# ProgrammateurFilPilote_1_2.net
KiCad netlist of a schematic drawn in EAGLE
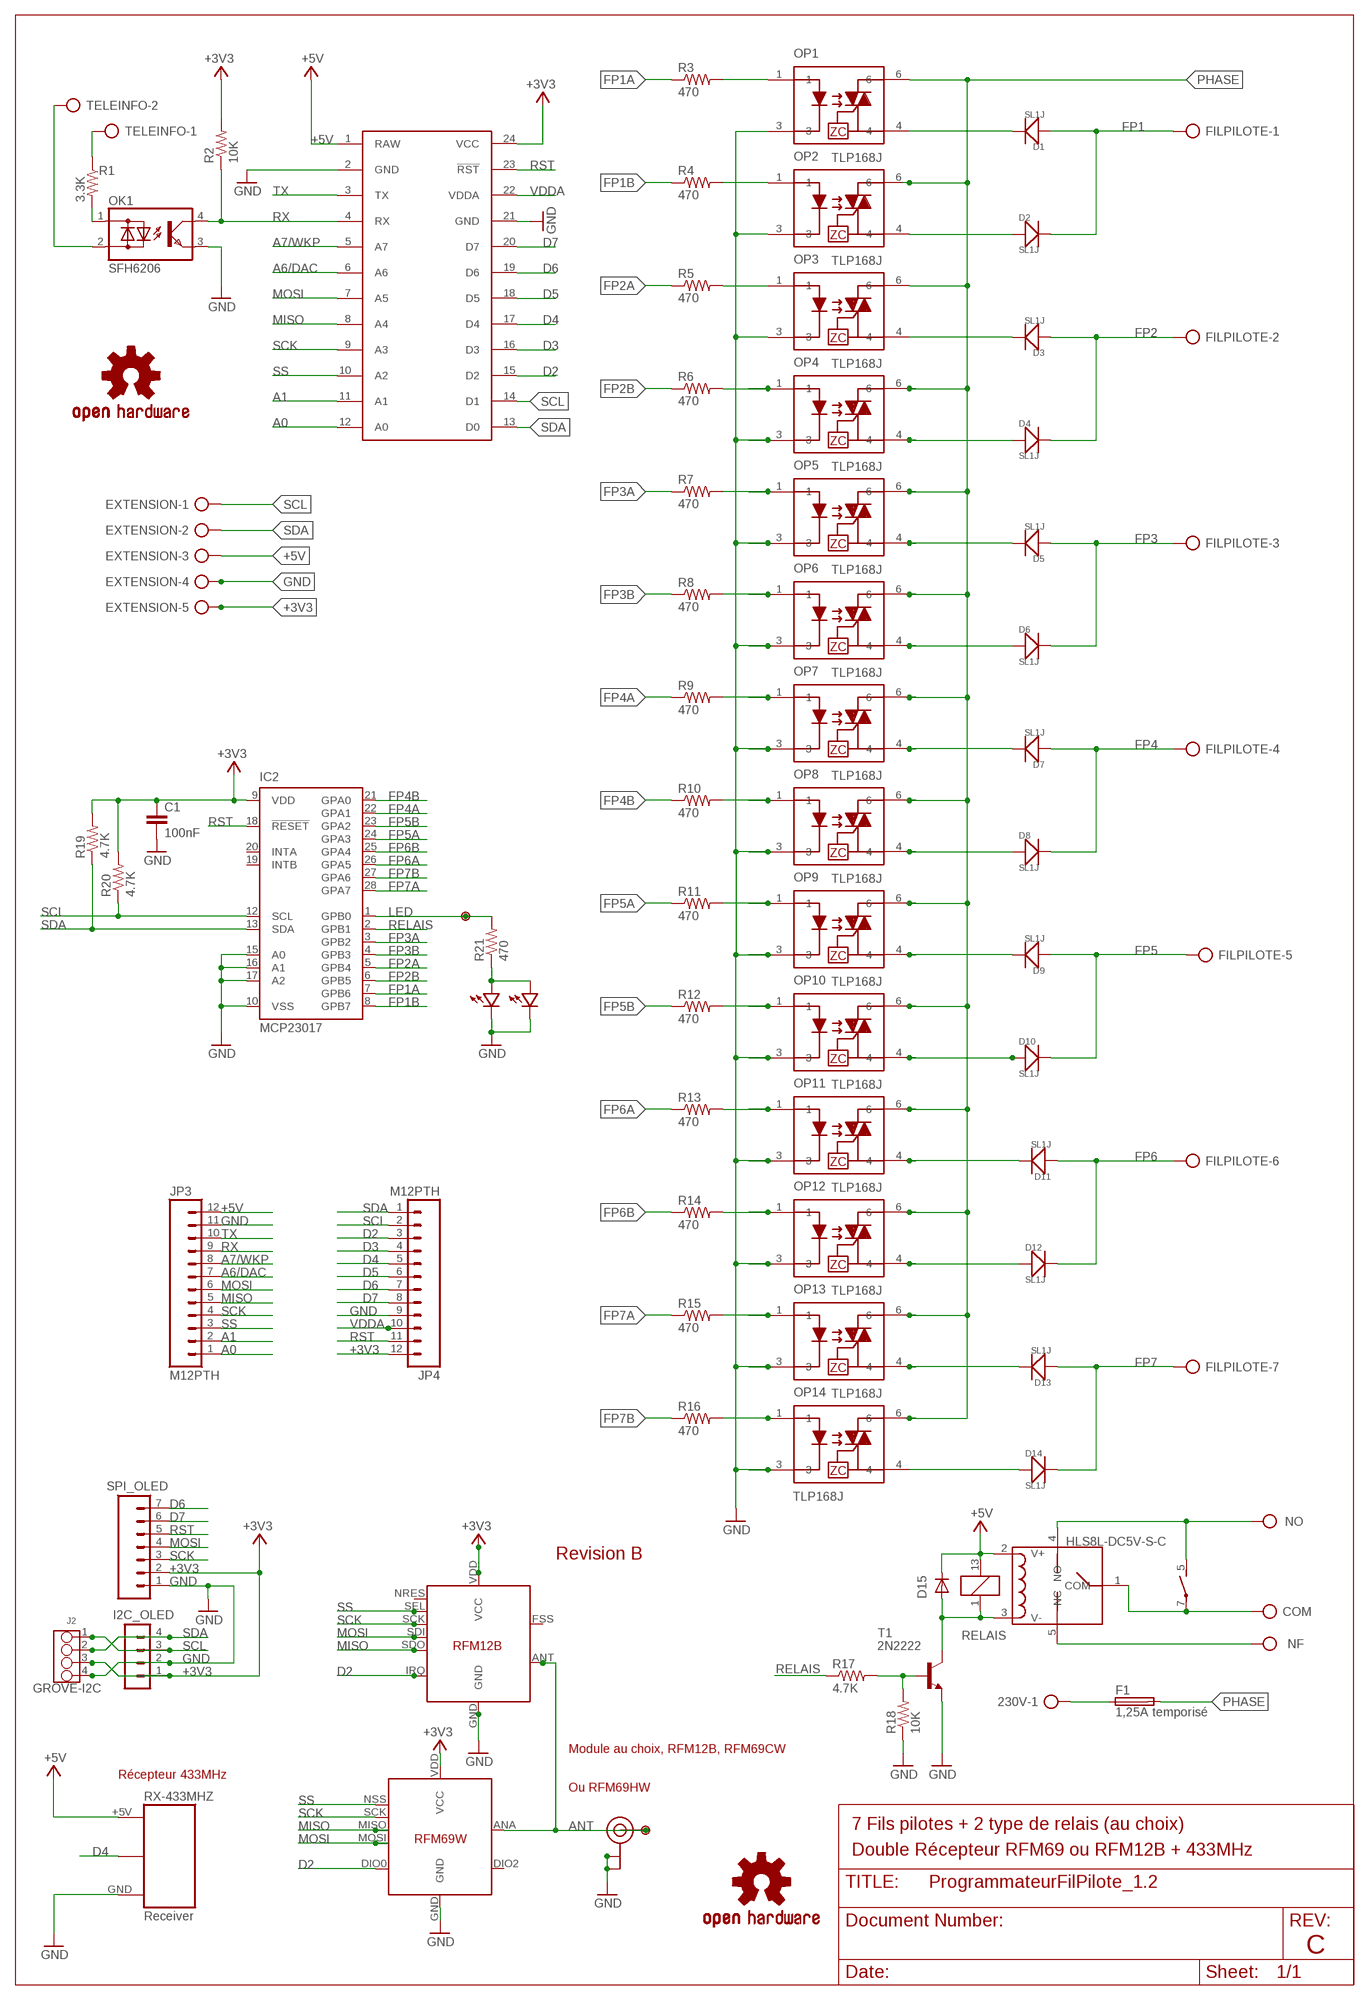
[diagram p0: schematic, sheet 1]

(export (version "E")
  (design (tool "Eeschema 10.0.6"))
  (components
    (comp (ref "230V")
      (value "AK500/2")
      (footprint "eagle-import:AK500_2")
      (libsource (lib "eagle-import") (part "AK500/2"))
    )
    (comp (ref "C1")
      (value "100nF")
      (footprint "eagle-import:1206-CAP")
      (libsource (lib "eagle-import") (part "CAP'1206-CAP'"))
    )
    (comp (ref "D1")
      (value "SL1J")
      (footprint "eagle-import:DO-214AC")
      (libsource (lib "eagle-import") (part "DIODE-SMA"))
    )
    (comp (ref "D2")
      (value "SL1J")
      (footprint "eagle-import:DO-214AC")
      (libsource (lib "eagle-import") (part "DIODE-SMA"))
    )
    (comp (ref "D3")
      (value "SL1J")
      (footprint "eagle-import:DO-214AC")
      (libsource (lib "eagle-import") (part "DIODE-SMA"))
    )
    (comp (ref "D4")
      (value "SL1J")
      (footprint "eagle-import:DO-214AC")
      (libsource (lib "eagle-import") (part "DIODE-SMA"))
    )
    (comp (ref "D5")
      (value "SL1J")
      (footprint "eagle-import:DO-214AC")
      (libsource (lib "eagle-import") (part "DIODE-SMA"))
    )
    (comp (ref "D6")
      (value "SL1J")
      (footprint "eagle-import:DO-214AC")
      (libsource (lib "eagle-import") (part "DIODE-SMA"))
    )
    (comp (ref "D7")
      (value "SL1J")
      (footprint "eagle-import:DO-214AC")
      (libsource (lib "eagle-import") (part "DIODE-SMA"))
    )
    (comp (ref "D8")
      (value "SL1J")
      (footprint "eagle-import:DO-214AC")
      (libsource (lib "eagle-import") (part "DIODE-SMA"))
    )
    (comp (ref "D9")
      (value "SL1J")
      (footprint "eagle-import:DO-214AC")
      (libsource (lib "eagle-import") (part "DIODE-SMA"))
    )
    (comp (ref "D10")
      (value "SL1J")
      (footprint "eagle-import:DO-214AC")
      (libsource (lib "eagle-import") (part "DIODE-SMA"))
    )
    (comp (ref "D11")
      (value "SL1J")
      (footprint "eagle-import:DO-214AC")
      (libsource (lib "eagle-import") (part "DIODE-SMA"))
    )
    (comp (ref "D12")
      (value "SL1J")
      (footprint "eagle-import:DO-214AC")
      (libsource (lib "eagle-import") (part "DIODE-SMA"))
    )
    (comp (ref "D13")
      (value "SL1J")
      (footprint "eagle-import:DO-214AC")
      (libsource (lib "eagle-import") (part "DIODE-SMA"))
    )
    (comp (ref "D14")
      (value "SL1J")
      (footprint "eagle-import:DO-214AC")
      (libsource (lib "eagle-import") (part "DIODE-SMA"))
    )
    (comp (ref "D15")
      (value "CGRM4001-G")
      (footprint "eagle-import:SOD-123_MINI-SMA")
      (libsource (lib "eagle-import") (part "CGRM400-G1"))
    )
    (comp (ref "EXTENSION")
      (value "AK500/5")
      (footprint "eagle-import:AK500_5")
      (libsource (lib "eagle-import") (part "AK500/5"))
    )
    (comp (ref "F1")
      (value "1,25A temporisé")
      (footprint "eagle-import:TE5")
      (libsource (lib "eagle-import") (part "TE5"))
    )
    (comp (ref "FILPILOTE")
      (value "AK500/7")
      (footprint "eagle-import:AK500_7")
      (libsource (lib "eagle-import") (part "AK500/7"))
    )
    (comp (ref "I2C_OLED")
      (value "CON_HEADER_1X04'SMALL''")
      (footprint "eagle-import:M1X4")
      (libsource (lib "eagle-import") (part "CON_HEADER_1X04'SMALL''"))
    )
    (comp (ref "IC2")
      (value "MCP23017")
      (footprint "eagle-import:DIL28-3")
      (libsource (lib "eagle-import") (part "MCP23017SP"))
    )
    (comp (ref "J2")
      (value "GROVE-I2C")
      (footprint "eagle-import:4P-2.0")
      (libsource (lib "eagle-import") (part "GROVE-4P-2.0-3470130P1"))
    )
    (comp (ref "JP3")
      (value "M12PTH")
      (footprint "eagle-import:1X12-SMALL-PADS")
      (libsource (lib "eagle-import") (part "M12PTH"))
    )
    (comp (ref "JP4")
      (value "M12PTH")
      (footprint "eagle-import:1X12-SMALL-PADS")
      (libsource (lib "eagle-import") (part "M12PTH"))
    )
    (comp (ref "L")
      (value "LED0805-LARGE")
      (footprint "eagle-import:0805-LED-LARGEPADS")
      (libsource (lib "eagle-import") (part "LED0805-LARGE"))
    )
    (comp (ref "LED")
      (value "LED3MMNOSILK")
      (footprint "eagle-import:LED3MM_NOSILK")
      (libsource (lib "eagle-import") (part "LED3MMNOSILK"))
    )
    (comp (ref "LOGO1")
      (value "OSHW-LOGOL")
      (footprint "eagle-import:OSHW-LOGO-L")
      (libsource (lib "eagle-import") (part "OSHW-LOGOL"))
    )
    (comp (ref "LOGO2")
      (value "OSHW-LOGOL")
      (footprint "eagle-import:OSHW-LOGO-L")
      (libsource (lib "eagle-import") (part "OSHW-LOGOL"))
    )
    (comp (ref "OK1")
      (value "SFH6206")
      (footprint "eagle-import:DIL4-SMD")
      (fields (field (name "MF") "VISHAY/TELEFUNKEN") (field (name "MPN") "SFH6206-3"))
      (libsource (lib "eagle-import") (part "SFH6206"))
    )
    (comp (ref "OP1")
      (value "TLP168J")
      (footprint "eagle-import:MFSOP-4-HANDSOLDER")
      (libsource (lib "eagle-import") (part "TLP168JBIGPAD"))
    )
    (comp (ref "OP2")
      (value "TLP168J")
      (footprint "eagle-import:MFSOP-4-HANDSOLDER")
      (libsource (lib "eagle-import") (part "TLP168JBIGPAD"))
    )
    (comp (ref "OP3")
      (value "TLP168J")
      (footprint "eagle-import:MFSOP-4-HANDSOLDER")
      (libsource (lib "eagle-import") (part "TLP168JBIGPAD"))
    )
    (comp (ref "OP4")
      (value "TLP168J")
      (footprint "eagle-import:MFSOP-4-HANDSOLDER")
      (libsource (lib "eagle-import") (part "TLP168JBIGPAD"))
    )
    (comp (ref "OP5")
      (value "TLP168J")
      (footprint "eagle-import:MFSOP-4-HANDSOLDER")
      (libsource (lib "eagle-import") (part "TLP168JBIGPAD"))
    )
    (comp (ref "OP6")
      (value "TLP168J")
      (footprint "eagle-import:MFSOP-4-HANDSOLDER")
      (libsource (lib "eagle-import") (part "TLP168JBIGPAD"))
    )
    (comp (ref "OP7")
      (value "TLP168J")
      (footprint "eagle-import:MFSOP-4-HANDSOLDER")
      (libsource (lib "eagle-import") (part "TLP168JBIGPAD"))
    )
    (comp (ref "OP8")
      (value "TLP168J")
      (footprint "eagle-import:MFSOP-4-HANDSOLDER")
      (libsource (lib "eagle-import") (part "TLP168JBIGPAD"))
    )
    (comp (ref "OP9")
      (value "TLP168J")
      (footprint "eagle-import:MFSOP-4-HANDSOLDER")
      (libsource (lib "eagle-import") (part "TLP168JBIGPAD"))
    )
    (comp (ref "OP10")
      (value "TLP168J")
      (footprint "eagle-import:MFSOP-4-HANDSOLDER")
      (libsource (lib "eagle-import") (part "TLP168JBIGPAD"))
    )
    (comp (ref "OP11")
      (value "TLP168J")
      (footprint "eagle-import:MFSOP-4-HANDSOLDER")
      (libsource (lib "eagle-import") (part "TLP168JBIGPAD"))
    )
    (comp (ref "OP12")
      (value "TLP168J")
      (footprint "eagle-import:MFSOP-4-HANDSOLDER")
      (libsource (lib "eagle-import") (part "TLP168JBIGPAD"))
    )
    (comp (ref "OP13")
      (value "TLP168J")
      (footprint "eagle-import:MFSOP-4-HANDSOLDER")
      (libsource (lib "eagle-import") (part "TLP168JBIGPAD"))
    )
    (comp (ref "OP14")
      (value "TLP168J")
      (footprint "eagle-import:MFSOP-4-HANDSOLDER")
      (libsource (lib "eagle-import") (part "TLP168JBIGPAD"))
    )
    (comp (ref "P1")
      (value "PADSMALL")
      (footprint "eagle-import:PAD-SMALL")
      (libsource (lib "eagle-import") (part "PADSMALL"))
    )
    (comp (ref "P2")
      (value "PADSMALL")
      (footprint "eagle-import:PAD-SMALL")
      (libsource (lib "eagle-import") (part "PADSMALL"))
    )
    (comp (ref "R1")
      (value "3.3K")
      (footprint "eagle-import:1206-RES")
      (libsource (lib "eagle-import") (part "RESISTOR'1206-RES''"))
    )
    (comp (ref "R2")
      (value "10K")
      (footprint "eagle-import:1206-RES")
      (libsource (lib "eagle-import") (part "RESISTOR'1206-RES''"))
    )
    (comp (ref "R3")
      (value "470")
      (footprint "eagle-import:1206-RES")
      (libsource (lib "eagle-import") (part "RESISTOR'1206-RES''"))
    )
    (comp (ref "R4")
      (value "470")
      (footprint "eagle-import:1206-RES")
      (libsource (lib "eagle-import") (part "RESISTOR'1206-RES''"))
    )
    (comp (ref "R5")
      (value "470")
      (footprint "eagle-import:1206-RES")
      (libsource (lib "eagle-import") (part "RESISTOR'1206-RES''"))
    )
    (comp (ref "R6")
      (value "470")
      (footprint "eagle-import:1206-RES")
      (libsource (lib "eagle-import") (part "RESISTOR'1206-RES''"))
    )
    (comp (ref "R7")
      (value "470")
      (footprint "eagle-import:1206-RES")
      (libsource (lib "eagle-import") (part "RESISTOR'1206-RES''"))
    )
    (comp (ref "R8")
      (value "470")
      (footprint "eagle-import:1206-RES")
      (libsource (lib "eagle-import") (part "RESISTOR'1206-RES''"))
    )
    (comp (ref "R9")
      (value "470")
      (footprint "eagle-import:1206-RES")
      (libsource (lib "eagle-import") (part "RESISTOR'1206-RES''"))
    )
    (comp (ref "R10")
      (value "470")
      (footprint "eagle-import:1206-RES")
      (libsource (lib "eagle-import") (part "RESISTOR'1206-RES''"))
    )
    (comp (ref "R11")
      (value "470")
      (footprint "eagle-import:1206-RES")
      (libsource (lib "eagle-import") (part "RESISTOR'1206-RES''"))
    )
    (comp (ref "R12")
      (value "470")
      (footprint "eagle-import:1206-RES")
      (libsource (lib "eagle-import") (part "RESISTOR'1206-RES''"))
    )
    (comp (ref "R13")
      (value "470")
      (footprint "eagle-import:1206-RES")
      (libsource (lib "eagle-import") (part "RESISTOR'1206-RES''"))
    )
    (comp (ref "R14")
      (value "470")
      (footprint "eagle-import:1206-RES")
      (libsource (lib "eagle-import") (part "RESISTOR'1206-RES''"))
    )
    (comp (ref "R15")
      (value "470")
      (footprint "eagle-import:1206-RES")
      (libsource (lib "eagle-import") (part "RESISTOR'1206-RES''"))
    )
    (comp (ref "R16")
      (value "470")
      (footprint "eagle-import:1206-RES")
      (libsource (lib "eagle-import") (part "RESISTOR'1206-RES''"))
    )
    (comp (ref "R17")
      (value "4.7K")
      (footprint "eagle-import:1206-RES")
      (libsource (lib "eagle-import") (part "RESISTOR'1206-RES''"))
    )
    (comp (ref "R18")
      (value "10K")
      (footprint "eagle-import:1206-RES")
      (libsource (lib "eagle-import") (part "RESISTOR'1206-RES''"))
    )
    (comp (ref "R19")
      (value "4.7K")
      (footprint "eagle-import:1206-RES")
      (libsource (lib "eagle-import") (part "RESISTOR'1206-RES''"))
    )
    (comp (ref "R20")
      (value "4.7K")
      (footprint "eagle-import:1206-RES")
      (libsource (lib "eagle-import") (part "RESISTOR'1206-RES''"))
    )
    (comp (ref "R21")
      (value "470")
      (footprint "eagle-import:1206-RES")
      (libsource (lib "eagle-import") (part "RESISTOR'1206-RES''"))
    )
    (comp (ref "RELAIS")
      (value "Relais G6D")
      (footprint "eagle-import:G6D")
      (libsource (lib "eagle-import") (part "G6D?-1A-ASI12VDC"))
    )
    (comp (ref "RL")
      (value "AK500/2")
      (footprint "eagle-import:AK500_2")
      (libsource (lib "eagle-import") (part "AK500/2"))
    )
    (comp (ref "RX-433MHZ")
      (value "Receiver")
      (footprint "eagle-import:RF-LINK_RX")
      (libsource (lib "eagle-import") (part "RF-LINK_RX"))
    )
    (comp (ref "SPARKCORE")
      (value "SPARK_CORECORE")
      (footprint "eagle-import:SPARK_CORE")
      (libsource (lib "eagle-import") (part "SPARK_CORECORE"))
    )
    (comp (ref "SPI_OLED")
      (value "CON_HEADER_1X07'SMALL'")
      (footprint "eagle-import:M1X7")
      (libsource (lib "eagle-import") (part "CON_HEADER_1X07'SMALL'"))
    )
    (comp (ref "SW1")
      (value "HLS8L-DC5V-S-C")
      (footprint "eagle-import:5P-L19.0XW15.0XH15.0MM")
      (libsource (lib "eagle-import") (part "RELAY-HLS8L-DC5V-S-C-315030000"))
    )
    (comp (ref "T1")
      (value "2N2222")
      (footprint "eagle-import:TO92-EBC")
      (libsource (lib "eagle-import") (part "-NPN-TO92-EBC2N2222"))
    )
    (comp (ref "TELEINFO")
      (value "AK500/2")
      (footprint "eagle-import:AK500_2")
      (libsource (lib "eagle-import") (part "AK500/2"))
    )
    (comp (ref "U$2")
      (value "RFM12B")
      (footprint "eagle-import:RFM12B-MINPADS")
      (libsource (lib "eagle-import") (part "RFM12B"))
    )
    (comp (ref "U$3")
      (value "RFM69W")
      (footprint "eagle-import:RFM69W-MINPADS")
      (libsource (lib "eagle-import") (part "RFM69W"))
    )
    (comp (ref "U-FL")
      (value "U.FL")
      (footprint "eagle-import:U.FL")
      (libsource (lib "eagle-import") (part "U.FL"))
    )
  )
  (nets
    (net (code "1") (name "+3V3") (class "Default")
      (node (ref "C1") (pin "1") (pinfunction "1_1") (pintype "passive"))
      (node (ref "EXTENSION") (pin "5") (pinfunction "KL_5") (pintype "passive"))
      (node (ref "I2C_OLED") (pin "1") (pinfunction "1_1") (pintype "passive"))
      (node (ref "IC2") (pin "9") (pinfunction "VDD_9") (pintype "power_in"))
      (node (ref "J2") (pin "3") (pinfunction "3_3") (pintype "bidirectional"))
      (node (ref "JP4") (pin "12") (pinfunction "12_12") (pintype "passive"))
      (node (ref "R19") (pin "2") (pinfunction "2_2") (pintype "passive"))
      (node (ref "R2") (pin "2") (pinfunction "2_2") (pintype "passive"))
      (node (ref "R20") (pin "2") (pinfunction "2_2") (pintype "passive"))
      (node (ref "SPARKCORE") (pin "24") (pinfunction "VCC_24") (pintype "power_in"))
      (node (ref "SPI_OLED") (pin "2") (pinfunction "2_2") (pintype "passive"))
      (node (ref "U$2") (pin "VDD") (pinfunction "VCC_VDD") (pintype "power_in"))
      (node (ref "U$3") (pin "VDD") (pinfunction "VCC_VDD") (pintype "power_in"))
    )
    (net (code "2") (name "+5V") (class "Default")
      (node (ref "D15") (pin "C") (pinfunction "C_C") (pintype "passive"))
      (node (ref "EXTENSION") (pin "3") (pinfunction "KL_3") (pintype "passive"))
      (node (ref "JP3") (pin "12") (pinfunction "12_12") (pintype "passive"))
      (node (ref "RELAIS") (pin "13") (pinfunction "2_13") (pintype "passive"))
      (node (ref "RX-433MHZ") (pin "+5V") (pinfunction "+5V_+5V") (pintype "power_in"))
      (node (ref "SPARKCORE") (pin "1") (pinfunction "RAW_1") (pintype "power_in"))
      (node (ref "SW1") (pin "2") (pinfunction "V+_2") (pintype "bidirectional"))
    )
    (net (code "3") (name "/A0") (class "Default")
      (node (ref "JP3") (pin "1") (pinfunction "1_1") (pintype "passive"))
      (node (ref "SPARKCORE") (pin "12") (pinfunction "A0_12") (pintype "bidirectional"))
    )
    (net (code "4") (name "/A1") (class "Default")
      (node (ref "JP3") (pin "2") (pinfunction "2_2") (pintype "passive"))
      (node (ref "SPARKCORE") (pin "11") (pinfunction "A1_11") (pintype "bidirectional"))
    )
    (net (code "5") (name "/A6{slash}DAC") (class "Default")
      (node (ref "JP3") (pin "7") (pinfunction "7_7") (pintype "passive"))
      (node (ref "SPARKCORE") (pin "6") (pinfunction "A6_6") (pintype "bidirectional"))
    )
    (net (code "6") (name "/A7{slash}WKP") (class "Default")
      (node (ref "JP3") (pin "8") (pinfunction "8_8") (pintype "passive"))
      (node (ref "SPARKCORE") (pin "5") (pinfunction "A7_5") (pintype "bidirectional"))
    )
    (net (code "7") (name "/ANT") (class "Default")
      (node (ref "P1") (pin "1") (pinfunction "1_1") (pintype "bidirectional"))
      (node (ref "U$2") (pin "ANT") (pinfunction "ANT_ANT") (pintype "passive"))
      (node (ref "U$3") (pin "ANA") (pinfunction "ANT_ANA") (pintype "passive"))
      (node (ref "U-FL") (pin "3") (pinfunction "SIGNAL_3") (pintype "passive"))
    )
    (net (code "8") (name "/COM") (class "Default")
      (node (ref "RELAIS") (pin "7") (pinfunction "P_7") (pintype "passive"))
      (node (ref "RL") (pin "1") (pinfunction "KL_1") (pintype "passive"))
      (node (ref "SW1") (pin "1") (pinfunction "COM_1") (pintype "bidirectional"))
    )
    (net (code "9") (name "/D2") (class "Default")
      (node (ref "JP4") (pin "3") (pinfunction "3_3") (pintype "passive"))
      (node (ref "SPARKCORE") (pin "15") (pinfunction "D2_15") (pintype "bidirectional"))
      (node (ref "U$2") (pin "IRQ") (pinfunction "IRQ_IRQ") (pintype "open_collector"))
      (node (ref "U$3") (pin "DIO0") (pinfunction "DIO0_DIO0") (pintype "open_collector"))
    )
    (net (code "10") (name "/D3") (class "Default")
      (node (ref "JP4") (pin "4") (pinfunction "4_4") (pintype "passive"))
      (node (ref "SPARKCORE") (pin "16") (pinfunction "D3_16") (pintype "bidirectional"))
    )
    (net (code "11") (name "/D4") (class "Default")
      (node (ref "JP4") (pin "5") (pinfunction "5_5") (pintype "passive"))
      (node (ref "RX-433MHZ") (pin "DATA@1") (pinfunction "DATA_DATA@1") (pintype "output"))
      (node (ref "RX-433MHZ") (pin "DATA@2") (pinfunction "DATA_DATA@2") (pintype "output"))
      (node (ref "SPARKCORE") (pin "17") (pinfunction "D4_17") (pintype "bidirectional"))
    )
    (net (code "12") (name "/D5") (class "Default")
      (node (ref "JP4") (pin "6") (pinfunction "6_6") (pintype "passive"))
      (node (ref "SPARKCORE") (pin "18") (pinfunction "D5_18") (pintype "bidirectional"))
    )
    (net (code "13") (name "/D6") (class "Default")
      (node (ref "JP4") (pin "7") (pinfunction "7_7") (pintype "passive"))
      (node (ref "SPARKCORE") (pin "19") (pinfunction "D6_19") (pintype "bidirectional"))
      (node (ref "SPI_OLED") (pin "7") (pinfunction "7_7") (pintype "passive"))
    )
    (net (code "14") (name "/D7") (class "Default")
      (node (ref "JP4") (pin "8") (pinfunction "8_8") (pintype "passive"))
      (node (ref "SPARKCORE") (pin "20") (pinfunction "D7_20") (pintype "bidirectional"))
      (node (ref "SPI_OLED") (pin "6") (pinfunction "6_6") (pintype "passive"))
    )
    (net (code "15") (name "/FP1") (class "Default")
      (node (ref "D1") (pin "1") (pinfunction "+_1") (pintype "passive"))
      (node (ref "D2") (pin "2") (pinfunction "-_2") (pintype "passive"))
      (node (ref "FILPILOTE") (pin "1") (pinfunction "KL_1") (pintype "passive"))
    )
    (net (code "16") (name "/FP2") (class "Default")
      (node (ref "D3") (pin "1") (pinfunction "+_1") (pintype "passive"))
      (node (ref "D4") (pin "2") (pinfunction "-_2") (pintype "passive"))
      (node (ref "FILPILOTE") (pin "2") (pinfunction "KL_2") (pintype "passive"))
    )
    (net (code "17") (name "/FP3") (class "Default")
      (node (ref "D5") (pin "1") (pinfunction "+_1") (pintype "passive"))
      (node (ref "D6") (pin "2") (pinfunction "-_2") (pintype "passive"))
      (node (ref "FILPILOTE") (pin "3") (pinfunction "KL_3") (pintype "passive"))
    )
    (net (code "18") (name "/FP4") (class "Default")
      (node (ref "D7") (pin "1") (pinfunction "+_1") (pintype "passive"))
      (node (ref "D8") (pin "2") (pinfunction "-_2") (pintype "passive"))
      (node (ref "FILPILOTE") (pin "4") (pinfunction "KL_4") (pintype "passive"))
    )
    (net (code "19") (name "/FP5") (class "Default")
      (node (ref "D10") (pin "2") (pinfunction "-_2") (pintype "passive"))
      (node (ref "D9") (pin "1") (pinfunction "+_1") (pintype "passive"))
      (node (ref "FILPILOTE") (pin "5") (pinfunction "KL_5") (pintype "passive"))
    )
    (net (code "20") (name "/FP6") (class "Default")
      (node (ref "D11") (pin "1") (pinfunction "+_1") (pintype "passive"))
      (node (ref "D12") (pin "2") (pinfunction "-_2") (pintype "passive"))
      (node (ref "FILPILOTE") (pin "6") (pinfunction "KL_6") (pintype "passive"))
    )
    (net (code "21") (name "/FP7") (class "Default")
      (node (ref "D13") (pin "1") (pinfunction "+_1") (pintype "passive"))
      (node (ref "D14") (pin "2") (pinfunction "-_2") (pintype "passive"))
      (node (ref "FILPILOTE") (pin "7") (pinfunction "KL_7") (pintype "passive"))
    )
    (net (code "22") (name "/LED") (class "Default")
      (node (ref "IC2") (pin "1") (pinfunction "GPB0_1") (pintype "bidirectional"))
      (node (ref "P2") (pin "1") (pinfunction "1_1") (pintype "bidirectional"))
      (node (ref "R21") (pin "2") (pinfunction "2_2") (pintype "passive"))
    )
    (net (code "23") (name "/MISO") (class "Default")
      (node (ref "JP3") (pin "5") (pinfunction "5_5") (pintype "passive"))
      (node (ref "SPARKCORE") (pin "8") (pinfunction "A4_8") (pintype "bidirectional"))
      (node (ref "U$2") (pin "SDO") (pinfunction "SDO_SDO") (pintype "output"))
      (node (ref "U$3") (pin "MISO") (pinfunction "MISO_MISO") (pintype "input"))
    )
    (net (code "24") (name "/MOSI") (class "Default")
      (node (ref "JP3") (pin "6") (pinfunction "6_6") (pintype "passive"))
      (node (ref "SPARKCORE") (pin "7") (pinfunction "A5_7") (pintype "bidirectional"))
      (node (ref "SPI_OLED") (pin "4") (pinfunction "4_4") (pintype "passive"))
      (node (ref "U$2") (pin "SDI") (pinfunction "SDI_SDI") (pintype "input"))
      (node (ref "U$3") (pin "MOSI") (pinfunction "MOSI_MOSI") (pintype "output"))
    )
    (net (code "25") (name "/NF") (class "Default")
      (node (ref "RL") (pin "2") (pinfunction "KL_2") (pintype "passive"))
      (node (ref "SW1") (pin "5") (pinfunction "NC_5") (pintype "bidirectional"))
    )
    (net (code "26") (name "/NO") (class "Default")
      (node (ref "230V") (pin "2") (pinfunction "KL_2") (pintype "passive"))
      (node (ref "RELAIS") (pin "5") (pinfunction "S_5") (pintype "passive"))
      (node (ref "SW1") (pin "4") (pinfunction "NO_4") (pintype "bidirectional"))
    )
    (net (code "27") (name "/RELAIS") (class "Default")
      (node (ref "IC2") (pin "2") (pinfunction "GPB1_2") (pintype "bidirectional"))
      (node (ref "R17") (pin "1") (pinfunction "1_1") (pintype "passive"))
    )
    (net (code "28") (name "/RST") (class "Default")
      (node (ref "IC2") (pin "18") (pinfunction "~{RESET}_18") (pintype "input"))
      (node (ref "JP4") (pin "11") (pinfunction "11_11") (pintype "passive"))
      (node (ref "SPARKCORE") (pin "23") (pinfunction "~{RST}_23") (pintype "bidirectional"))
      (node (ref "SPI_OLED") (pin "5") (pinfunction "5_5") (pintype "passive"))
    )
    (net (code "29") (name "/RX") (class "Default")
      (node (ref "JP3") (pin "9") (pinfunction "9_9") (pintype "passive"))
      (node (ref "OK1") (pin "4") (pinfunction "C_4") (pintype "passive"))
      (node (ref "R2") (pin "1") (pinfunction "1_1") (pintype "passive"))
      (node (ref "SPARKCORE") (pin "4") (pinfunction "RX_4") (pintype "bidirectional"))
    )
    (net (code "30") (name "/SCK") (class "Default")
      (node (ref "JP3") (pin "4") (pinfunction "4_4") (pintype "passive"))
      (node (ref "SPARKCORE") (pin "9") (pinfunction "A3_9") (pintype "bidirectional"))
      (node (ref "SPI_OLED") (pin "3") (pinfunction "3_3") (pintype "passive"))
      (node (ref "U$2") (pin "SCK") (pinfunction "SCK_SCK") (pintype "input"))
      (node (ref "U$3") (pin "SCK") (pinfunction "SCK_SCK") (pintype "input"))
    )
    (net (code "31") (name "/SS") (class "Default")
      (node (ref "JP3") (pin "3") (pinfunction "3_3") (pintype "passive"))
      (node (ref "SPARKCORE") (pin "10") (pinfunction "A2_10") (pintype "bidirectional"))
      (node (ref "U$2") (pin "SEL") (pinfunction "SEL_SEL") (pintype "input"))
      (node (ref "U$3") (pin "NSS") (pinfunction "SEL_NSS") (pintype "input"))
    )
    (net (code "32") (name "/TX") (class "Default")
      (node (ref "JP3") (pin "10") (pinfunction "10_10") (pintype "passive"))
      (node (ref "SPARKCORE") (pin "3") (pinfunction "TX_3") (pintype "bidirectional"))
    )
    (net (code "33") (name "/VDDA") (class "Default")
      (node (ref "JP4") (pin "10") (pinfunction "10_10") (pintype "passive"))
      (node (ref "SPARKCORE") (pin "22") (pinfunction "VDDA_22") (pintype "power_in"))
    )
    (net (code "34") (name "FP1A") (class "Default")
      (node (ref "IC2") (pin "7") (pinfunction "GPB6_7") (pintype "bidirectional"))
      (node (ref "R3") (pin "1") (pinfunction "1_1") (pintype "passive"))
    )
    (net (code "35") (name "FP1B") (class "Default")
      (node (ref "IC2") (pin "8") (pinfunction "GPB7_8") (pintype "bidirectional"))
      (node (ref "R4") (pin "1") (pinfunction "1_1") (pintype "passive"))
    )
    (net (code "36") (name "FP2A") (class "Default")
      (node (ref "IC2") (pin "5") (pinfunction "GPB4_5") (pintype "bidirectional"))
      (node (ref "R5") (pin "1") (pinfunction "1_1") (pintype "passive"))
    )
    (net (code "37") (name "FP2B") (class "Default")
      (node (ref "IC2") (pin "6") (pinfunction "GPB5_6") (pintype "bidirectional"))
      (node (ref "R6") (pin "1") (pinfunction "1_1") (pintype "passive"))
    )
    (net (code "38") (name "FP3A") (class "Default")
      (node (ref "IC2") (pin "3") (pinfunction "GPB2_3") (pintype "bidirectional"))
      (node (ref "R7") (pin "1") (pinfunction "1_1") (pintype "passive"))
    )
    (net (code "39") (name "FP3B") (class "Default")
      (node (ref "IC2") (pin "4") (pinfunction "GPB3_4") (pintype "bidirectional"))
      (node (ref "R8") (pin "1") (pinfunction "1_1") (pintype "passive"))
    )
    (net (code "40") (name "FP4A") (class "Default")
      (node (ref "IC2") (pin "22") (pinfunction "GPA1_22") (pintype "bidirectional"))
      (node (ref "R9") (pin "1") (pinfunction "1_1") (pintype "passive"))
    )
    (net (code "41") (name "FP4B") (class "Default")
      (node (ref "IC2") (pin "21") (pinfunction "GPA0_21") (pintype "bidirectional"))
      (node (ref "R10") (pin "1") (pinfunction "1_1") (pintype "passive"))
    )
    (net (code "42") (name "FP5A") (class "Default")
      (node (ref "IC2") (pin "24") (pinfunction "GPA3_24") (pintype "bidirectional"))
      (node (ref "R11") (pin "1") (pinfunction "1_1") (pintype "passive"))
    )
    (net (code "43") (name "FP5B") (class "Default")
      (node (ref "IC2") (pin "23") (pinfunction "GPA2_23") (pintype "bidirectional"))
      (node (ref "R12") (pin "1") (pinfunction "1_1") (pintype "passive"))
    )
    (net (code "44") (name "FP6A") (class "Default")
      (node (ref "IC2") (pin "26") (pinfunction "GPA5_26") (pintype "bidirectional"))
      (node (ref "R13") (pin "1") (pinfunction "1_1") (pintype "passive"))
    )
    (net (code "45") (name "FP6B") (class "Default")
      (node (ref "IC2") (pin "25") (pinfunction "GPA4_25") (pintype "bidirectional"))
      (node (ref "R14") (pin "1") (pinfunction "1_1") (pintype "passive"))
    )
    (net (code "46") (name "FP7A") (class "Default")
      (node (ref "IC2") (pin "28") (pinfunction "GPA7_28") (pintype "bidirectional"))
      (node (ref "R15") (pin "1") (pinfunction "1_1") (pintype "passive"))
    )
    (net (code "47") (name "FP7B") (class "Default")
      (node (ref "IC2") (pin "27") (pinfunction "GPA6_27") (pintype "bidirectional"))
      (node (ref "R16") (pin "1") (pinfunction "1_1") (pintype "passive"))
    )
    (net (code "48") (name "GND") (class "Default")
      (node (ref "C1") (pin "2") (pinfunction "2_2") (pintype "passive"))
      (node (ref "EXTENSION") (pin "4") (pinfunction "KL_4") (pintype "passive"))
      (node (ref "I2C_OLED") (pin "2") (pinfunction "2_2") (pintype "passive"))
      (node (ref "IC2") (pin "10") (pinfunction "VSS_10") (pintype "power_in"))
      (node (ref "IC2") (pin "15") (pinfunction "A0_15") (pintype "input"))
      (node (ref "IC2") (pin "16") (pinfunction "A1_16") (pintype "input"))
      (node (ref "IC2") (pin "17") (pinfunction "A2_17") (pintype "input"))
      (node (ref "J2") (pin "4") (pinfunction "4_4") (pintype "bidirectional"))
      (node (ref "JP3") (pin "11") (pinfunction "11_11") (pintype "passive"))
      (node (ref "JP4") (pin "9") (pinfunction "9_9") (pintype "passive"))
      (node (ref "L") (pin "MINUS") (pinfunction "MINUS_MINUS") (pintype "passive"))
      (node (ref "LED") (pin "MINUS") (pinfunction "MINUS_MINUS") (pintype "passive"))
      (node (ref "OK1") (pin "3") (pinfunction "E_3") (pintype "passive"))
      (node (ref "OP1") (pin "3") (pinfunction "3_3") (pintype "bidirectional"))
      (node (ref "OP10") (pin "3") (pinfunction "3_3") (pintype "bidirectional"))
      (node (ref "OP11") (pin "3") (pinfunction "3_3") (pintype "bidirectional"))
      (node (ref "OP12") (pin "3") (pinfunction "3_3") (pintype "bidirectional"))
      (node (ref "OP13") (pin "3") (pinfunction "3_3") (pintype "bidirectional"))
      (node (ref "OP14") (pin "3") (pinfunction "3_3") (pintype "bidirectional"))
      (node (ref "OP2") (pin "3") (pinfunction "3_3") (pintype "bidirectional"))
      (node (ref "OP3") (pin "3") (pinfunction "3_3") (pintype "bidirectional"))
      (node (ref "OP4") (pin "3") (pinfunction "3_3") (pintype "bidirectional"))
      (node (ref "OP5") (pin "3") (pinfunction "3_3") (pintype "bidirectional"))
      (node (ref "OP6") (pin "3") (pinfunction "3_3") (pintype "bidirectional"))
      (node (ref "OP7") (pin "3") (pinfunction "3_3") (pintype "bidirectional"))
      (node (ref "OP8") (pin "3") (pinfunction "3_3") (pintype "bidirectional"))
      (node (ref "OP9") (pin "3") (pinfunction "3_3") (pintype "bidirectional"))
      (node (ref "R18") (pin "1") (pinfunction "1_1") (pintype "passive"))
      (node (ref "RX-433MHZ") (pin "GND") (pinfunction "GND_GND") (pintype "power_in"))
      (node (ref "SPARKCORE") (pin "2") (pinfunction "GND_2") (pintype "power_in"))
      (node (ref "SPARKCORE") (pin "21") (pinfunction "GND_21") (pintype "power_in"))
      (node (ref "SPI_OLED") (pin "1") (pinfunction "1_1") (pintype "passive"))
      (node (ref "T1") (pin "E") (pinfunction "E_E") (pintype "passive"))
      (node (ref "U$2") (pin "GND") (pinfunction "GND_GND") (pintype "power_in"))
      (node (ref "U$3") (pin "GND") (pinfunction "GND_GND") (pintype "power_in"))
      (node (ref "U-FL") (pin "1") (pinfunction "GND_1") (pintype "passive"))
      (node (ref "U-FL") (pin "2") (pinfunction "GND_2") (pintype "passive"))
    )
    (net (code "49") (name "Net-(230VA-KL)") (class "Default")
      (node (ref "230V") (pin "1") (pinfunction "KL_1") (pintype "passive"))
      (node (ref "F1") (pin "1") (pinfunction "1_1") (pintype "passive"))
    )
    (net (code "50") (name "Net-(D1--)") (class "Default")
      (node (ref "D1") (pin "2") (pinfunction "-_2") (pintype "passive"))
      (node (ref "OP1") (pin "4") (pinfunction "4_4") (pintype "bidirectional"))
    )
    (net (code "51") (name "Net-(D2-+)") (class "Default")
      (node (ref "D2") (pin "1") (pinfunction "+_1") (pintype "passive"))
      (node (ref "OP2") (pin "4") (pinfunction "4_4") (pintype "bidirectional"))
    )
    (net (code "52") (name "Net-(D3--)") (class "Default")
      (node (ref "D3") (pin "2") (pinfunction "-_2") (pintype "passive"))
      (node (ref "OP3") (pin "4") (pinfunction "4_4") (pintype "bidirectional"))
    )
    (net (code "53") (name "Net-(D4-+)") (class "Default")
      (node (ref "D4") (pin "1") (pinfunction "+_1") (pintype "passive"))
      (node (ref "OP4") (pin "4") (pinfunction "4_4") (pintype "bidirectional"))
    )
    (net (code "54") (name "Net-(D5--)") (class "Default")
      (node (ref "D5") (pin "2") (pinfunction "-_2") (pintype "passive"))
      (node (ref "OP5") (pin "4") (pinfunction "4_4") (pintype "bidirectional"))
    )
    (net (code "55") (name "Net-(D6-+)") (class "Default")
      (node (ref "D6") (pin "1") (pinfunction "+_1") (pintype "passive"))
      (node (ref "OP6") (pin "4") (pinfunction "4_4") (pintype "bidirectional"))
    )
    (net (code "56") (name "Net-(D7--)") (class "Default")
      (node (ref "D7") (pin "2") (pinfunction "-_2") (pintype "passive"))
      (node (ref "OP7") (pin "4") (pinfunction "4_4") (pintype "bidirectional"))
    )
    (net (code "57") (name "Net-(D8-+)") (class "Default")
      (node (ref "D8") (pin "1") (pinfunction "+_1") (pintype "passive"))
      (node (ref "OP8") (pin "4") (pinfunction "4_4") (pintype "bidirectional"))
    )
    (net (code "58") (name "Net-(D9--)") (class "Default")
      (node (ref "D9") (pin "2") (pinfunction "-_2") (pintype "passive"))
      (node (ref "OP9") (pin "4") (pinfunction "4_4") (pintype "bidirectional"))
    )
    (net (code "59") (name "Net-(D10-+)") (class "Default")
      (node (ref "D10") (pin "1") (pinfunction "+_1") (pintype "passive"))
      (node (ref "OP10") (pin "4") (pinfunction "4_4") (pintype "bidirectional"))
    )
    (net (code "60") (name "Net-(D11--)") (class "Default")
      (node (ref "D11") (pin "2") (pinfunction "-_2") (pintype "passive"))
      (node (ref "OP11") (pin "4") (pinfunction "4_4") (pintype "bidirectional"))
    )
    (net (code "61") (name "Net-(D12-+)") (class "Default")
      (node (ref "D12") (pin "1") (pinfunction "+_1") (pintype "passive"))
      (node (ref "OP12") (pin "4") (pinfunction "4_4") (pintype "bidirectional"))
    )
    (net (code "62") (name "Net-(D13--)") (class "Default")
      (node (ref "D13") (pin "2") (pinfunction "-_2") (pintype "passive"))
      (node (ref "OP13") (pin "4") (pinfunction "4_4") (pintype "bidirectional"))
    )
    (net (code "63") (name "Net-(D14-+)") (class "Default")
      (node (ref "D14") (pin "1") (pinfunction "+_1") (pintype "passive"))
      (node (ref "OP14") (pin "4") (pinfunction "4_4") (pintype "bidirectional"))
    )
    (net (code "64") (name "Net-(L-PadPLUS)") (class "Default")
      (node (ref "L") (pin "PLUS") (pinfunction "PLUS_PLUS") (pintype "passive"))
      (node (ref "LED") (pin "PLUS") (pinfunction "PLUS_PLUS") (pintype "passive"))
      (node (ref "R21") (pin "1") (pinfunction "1_1") (pintype "passive"))
    )
    (net (code "65") (name "Net-(OK1-AC1)") (class "Default")
      (node (ref "OK1") (pin "1") (pinfunction "AC1_1") (pintype "passive"))
      (node (ref "R1") (pin "2") (pinfunction "2_2") (pintype "passive"))
    )
    (net (code "66") (name "Net-(OK1-AC2)") (class "Default")
      (node (ref "OK1") (pin "2") (pinfunction "AC2_2") (pintype "passive"))
      (node (ref "TELEINFO") (pin "2") (pinfunction "KL_2") (pintype "passive"))
    )
    (net (code "67") (name "Net-(OP1-Pad1)") (class "Default")
      (node (ref "OP1") (pin "1") (pinfunction "1_1") (pintype "bidirectional"))
      (node (ref "R3") (pin "2") (pinfunction "2_2") (pintype "passive"))
    )
    (net (code "68") (name "Net-(OP2-Pad1)") (class "Default")
      (node (ref "OP2") (pin "1") (pinfunction "1_1") (pintype "bidirectional"))
      (node (ref "R4") (pin "2") (pinfunction "2_2") (pintype "passive"))
    )
    (net (code "69") (name "Net-(OP3-Pad1)") (class "Default")
      (node (ref "OP3") (pin "1") (pinfunction "1_1") (pintype "bidirectional"))
      (node (ref "R5") (pin "2") (pinfunction "2_2") (pintype "passive"))
    )
    (net (code "70") (name "Net-(OP4-Pad1)") (class "Default")
      (node (ref "OP4") (pin "1") (pinfunction "1_1") (pintype "bidirectional"))
      (node (ref "R6") (pin "2") (pinfunction "2_2") (pintype "passive"))
    )
    (net (code "71") (name "Net-(OP5-Pad1)") (class "Default")
      (node (ref "OP5") (pin "1") (pinfunction "1_1") (pintype "bidirectional"))
      (node (ref "R7") (pin "2") (pinfunction "2_2") (pintype "passive"))
    )
    (net (code "72") (name "Net-(OP6-Pad1)") (class "Default")
      (node (ref "OP6") (pin "1") (pinfunction "1_1") (pintype "bidirectional"))
      (node (ref "R8") (pin "2") (pinfunction "2_2") (pintype "passive"))
    )
    (net (code "73") (name "Net-(OP7-Pad1)") (class "Default")
      (node (ref "OP7") (pin "1") (pinfunction "1_1") (pintype "bidirectional"))
      (node (ref "R9") (pin "2") (pinfunction "2_2") (pintype "passive"))
    )
    (net (code "74") (name "Net-(OP8-Pad1)") (class "Default")
      (node (ref "OP8") (pin "1") (pinfunction "1_1") (pintype "bidirectional"))
      (node (ref "R10") (pin "2") (pinfunction "2_2") (pintype "passive"))
    )
    (net (code "75") (name "Net-(OP9-Pad1)") (class "Default")
      (node (ref "OP9") (pin "1") (pinfunction "1_1") (pintype "bidirectional"))
      (node (ref "R11") (pin "2") (pinfunction "2_2") (pintype "passive"))
    )
    (net (code "76") (name "Net-(OP10-Pad1)") (class "Default")
      (node (ref "OP10") (pin "1") (pinfunction "1_1") (pintype "bidirectional"))
      (node (ref "R12") (pin "2") (pinfunction "2_2") (pintype "passive"))
    )
    (net (code "77") (name "Net-(OP11-Pad1)") (class "Default")
      (node (ref "OP11") (pin "1") (pinfunction "1_1") (pintype "bidirectional"))
      (node (ref "R13") (pin "2") (pinfunction "2_2") (pintype "passive"))
    )
    (net (code "78") (name "Net-(OP12-Pad1)") (class "Default")
      (node (ref "OP12") (pin "1") (pinfunction "1_1") (pintype "bidirectional"))
      (node (ref "R14") (pin "2") (pinfunction "2_2") (pintype "passive"))
    )
    (net (code "79") (name "Net-(OP13-Pad1)") (class "Default")
      (node (ref "OP13") (pin "1") (pinfunction "1_1") (pintype "bidirectional"))
      (node (ref "R15") (pin "2") (pinfunction "2_2") (pintype "passive"))
    )
    (net (code "80") (name "Net-(OP14-Pad1)") (class "Default")
      (node (ref "OP14") (pin "1") (pinfunction "1_1") (pintype "bidirectional"))
      (node (ref "R16") (pin "2") (pinfunction "2_2") (pintype "passive"))
    )
    (net (code "81") (name "Net-(R17-Pad2)") (class "Default")
      (node (ref "R17") (pin "2") (pinfunction "2_2") (pintype "passive"))
      (node (ref "R18") (pin "2") (pinfunction "2_2") (pintype "passive"))
      (node (ref "T1") (pin "B") (pinfunction "B_B") (pintype "passive"))
    )
    (net (code "82") (name "Net-(SW1-V-)") (class "Default")
      (node (ref "D15") (pin "A") (pinfunction "A_A") (pintype "passive"))
      (node (ref "RELAIS") (pin "1") (pinfunction "1_1") (pintype "passive"))
      (node (ref "SW1") (pin "3") (pinfunction "V-_3") (pintype "bidirectional"))
      (node (ref "T1") (pin "C") (pinfunction "C_C") (pintype "passive"))
    )
    (net (code "83") (name "Net-(TELEINFOA-KL)") (class "Default")
      (node (ref "R1") (pin "1") (pinfunction "1_1") (pintype "passive"))
      (node (ref "TELEINFO") (pin "1") (pinfunction "KL_1") (pintype "passive"))
    )
    (net (code "84") (name "PHASE") (class "Default")
      (node (ref "F1") (pin "2") (pinfunction "2_2") (pintype "passive"))
      (node (ref "OP1") (pin "6") (pinfunction "6_6") (pintype "bidirectional"))
      (node (ref "OP10") (pin "6") (pinfunction "6_6") (pintype "bidirectional"))
      (node (ref "OP11") (pin "6") (pinfunction "6_6") (pintype "bidirectional"))
      (node (ref "OP12") (pin "6") (pinfunction "6_6") (pintype "bidirectional"))
      (node (ref "OP13") (pin "6") (pinfunction "6_6") (pintype "bidirectional"))
      (node (ref "OP14") (pin "6") (pinfunction "6_6") (pintype "bidirectional"))
      (node (ref "OP2") (pin "6") (pinfunction "6_6") (pintype "bidirectional"))
      (node (ref "OP3") (pin "6") (pinfunction "6_6") (pintype "bidirectional"))
      (node (ref "OP4") (pin "6") (pinfunction "6_6") (pintype "bidirectional"))
      (node (ref "OP5") (pin "6") (pinfunction "6_6") (pintype "bidirectional"))
      (node (ref "OP6") (pin "6") (pinfunction "6_6") (pintype "bidirectional"))
      (node (ref "OP7") (pin "6") (pinfunction "6_6") (pintype "bidirectional"))
      (node (ref "OP8") (pin "6") (pinfunction "6_6") (pintype "bidirectional"))
      (node (ref "OP9") (pin "6") (pinfunction "6_6") (pintype "bidirectional"))
    )
    (net (code "85") (name "SCL") (class "Default")
      (node (ref "EXTENSION") (pin "1") (pinfunction "KL_1") (pintype "passive"))
      (node (ref "I2C_OLED") (pin "3") (pinfunction "3_3") (pintype "passive"))
      (node (ref "IC2") (pin "12") (pinfunction "SCL_12") (pintype "input"))
      (node (ref "J2") (pin "1") (pinfunction "1_1") (pintype "bidirectional"))
      (node (ref "JP4") (pin "2") (pinfunction "2_2") (pintype "passive"))
      (node (ref "R20") (pin "1") (pinfunction "1_1") (pintype "passive"))
      (node (ref "SPARKCORE") (pin "14") (pinfunction "D1_14") (pintype "bidirectional"))
    )
    (net (code "86") (name "SDA") (class "Default")
      (node (ref "EXTENSION") (pin "2") (pinfunction "KL_2") (pintype "passive"))
      (node (ref "I2C_OLED") (pin "4") (pinfunction "4_4") (pintype "passive"))
      (node (ref "IC2") (pin "13") (pinfunction "SDA_13") (pintype "bidirectional"))
      (node (ref "J2") (pin "2") (pinfunction "2_2") (pintype "bidirectional"))
      (node (ref "JP4") (pin "1") (pinfunction "1_1") (pintype "passive"))
      (node (ref "R19") (pin "1") (pinfunction "1_1") (pintype "passive"))
      (node (ref "SPARKCORE") (pin "13") (pinfunction "D0_13") (pintype "bidirectional"))
    )
    (net (code "87") (name "unconnected-(IC2-INTA-Pad20)") (class "Default")
      (node (ref "IC2") (pin "20") (pinfunction "INTA_20") (pintype "output"))
    )
    (net (code "88") (name "unconnected-(IC2-INTB-Pad19)") (class "Default")
      (node (ref "IC2") (pin "19") (pinfunction "INTB_19") (pintype "output"))
    )
    (net (code "89") (name "unconnected-(U$2-FFS-PadFSS)") (class "Default")
      (node (ref "U$2") (pin "FSS") (pinfunction "FFS_FSS") (pintype "bidirectional"))
    )
    (net (code "90") (name "unconnected-(U$2-PadNRES)") (class "Default")
      (node (ref "U$2") (pin "NRES") (pinfunction "NRES_NRES") (pintype "input"))
    )
    (net (code "91") (name "unconnected-(U$3-PadDIO2)") (class "Default")
      (node (ref "U$3") (pin "DIO2") (pinfunction "DIO2_DIO2") (pintype "open_collector"))
    )
  )
)
